# Trevor-smt.net
KiCad netlist of a schematic drawn in EAGLE
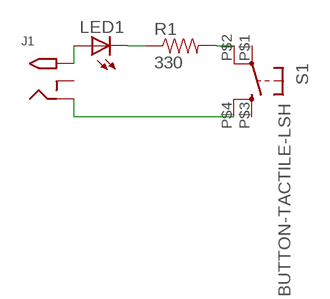
[diagram p0: schematic, sheet 1]

(export (version "E")
  (design (tool "Eeschema 10.0.6"))
  (components
    (comp (ref "J1")
      (value "2.1MMJACKTHM")
      (footprint "eagle-import:PJ-102A")
      (libsource (lib "eagle-import") (part "2.1MMJACKTHM"))
    )
    (comp (ref "LED1")
      (value "LED3MM")
      (footprint "eagle-import:LED3MM")
      (libsource (lib "eagle-import") (part "LED3MM"))
    )
    (comp (ref "R1")
      (value "330")
      (footprint "eagle-import:AXIAL-0.3")
      (libsource (lib "eagle-import") (part "RESISTORAXIAL-0.3"))
    )
    (comp (ref "S1")
      (value "BUTTON-TACTILE-LSH")
      (footprint "eagle-import:1301.9315")
      (libsource (lib "eagle-import") (part "BUTTON-TACTILE-LSH"))
    )
  )
  (nets
    (net (code "1") (name "Net-(J1-PadTIP)") (class "Default")
      (node (ref "J1") (pin "TIP") (pinfunction "TIP_TIP") (pintype "bidirectional"))
      (node (ref "LED1") (pin "A") (pinfunction "A_A") (pintype "passive"))
    )
    (net (code "2") (name "Net-(LED1-C)") (class "Default")
      (node (ref "LED1") (pin "K") (pinfunction "C_K") (pintype "passive"))
      (node (ref "R1") (pin "P$1") (pinfunction "1_P$1") (pintype "passive"))
    )
    (net (code "3") (name "Net-(R1-2)") (class "Default")
      (node (ref "R1") (pin "P$2") (pinfunction "2_P$2") (pintype "passive"))
      (node (ref "S1") (pin "P$2") (pinfunction "P1_P$2") (pintype "passive"))
    )
    (net (code "4") (name "Net-(S1-S1)") (class "Default")
      (node (ref "J1") (pin "RING") (pinfunction "RING_RING") (pintype "bidirectional"))
      (node (ref "S1") (pin "P$4") (pinfunction "S1_P$4") (pintype "passive"))
    )
    (net (code "5") (name "unconnected-(J1-PadRING_SW)") (class "Default")
      (node (ref "J1") (pin "RING_SW") (pinfunction "RING_SW_RING_SW") (pintype "bidirectional"))
    )
    (net (code "6") (name "unconnected-(S1-P-PadP$1)") (class "Default")
      (node (ref "S1") (pin "P$1") (pinfunction "P_P$1") (pintype "passive"))
    )
    (net (code "7") (name "unconnected-(S1-S-PadP$3)") (class "Default")
      (node (ref "S1") (pin "P$3") (pinfunction "S_P$3") (pintype "passive"))
    )
  )
)
